# xnemo.net
KiCad netlist of a schematic drawn in EAGLE
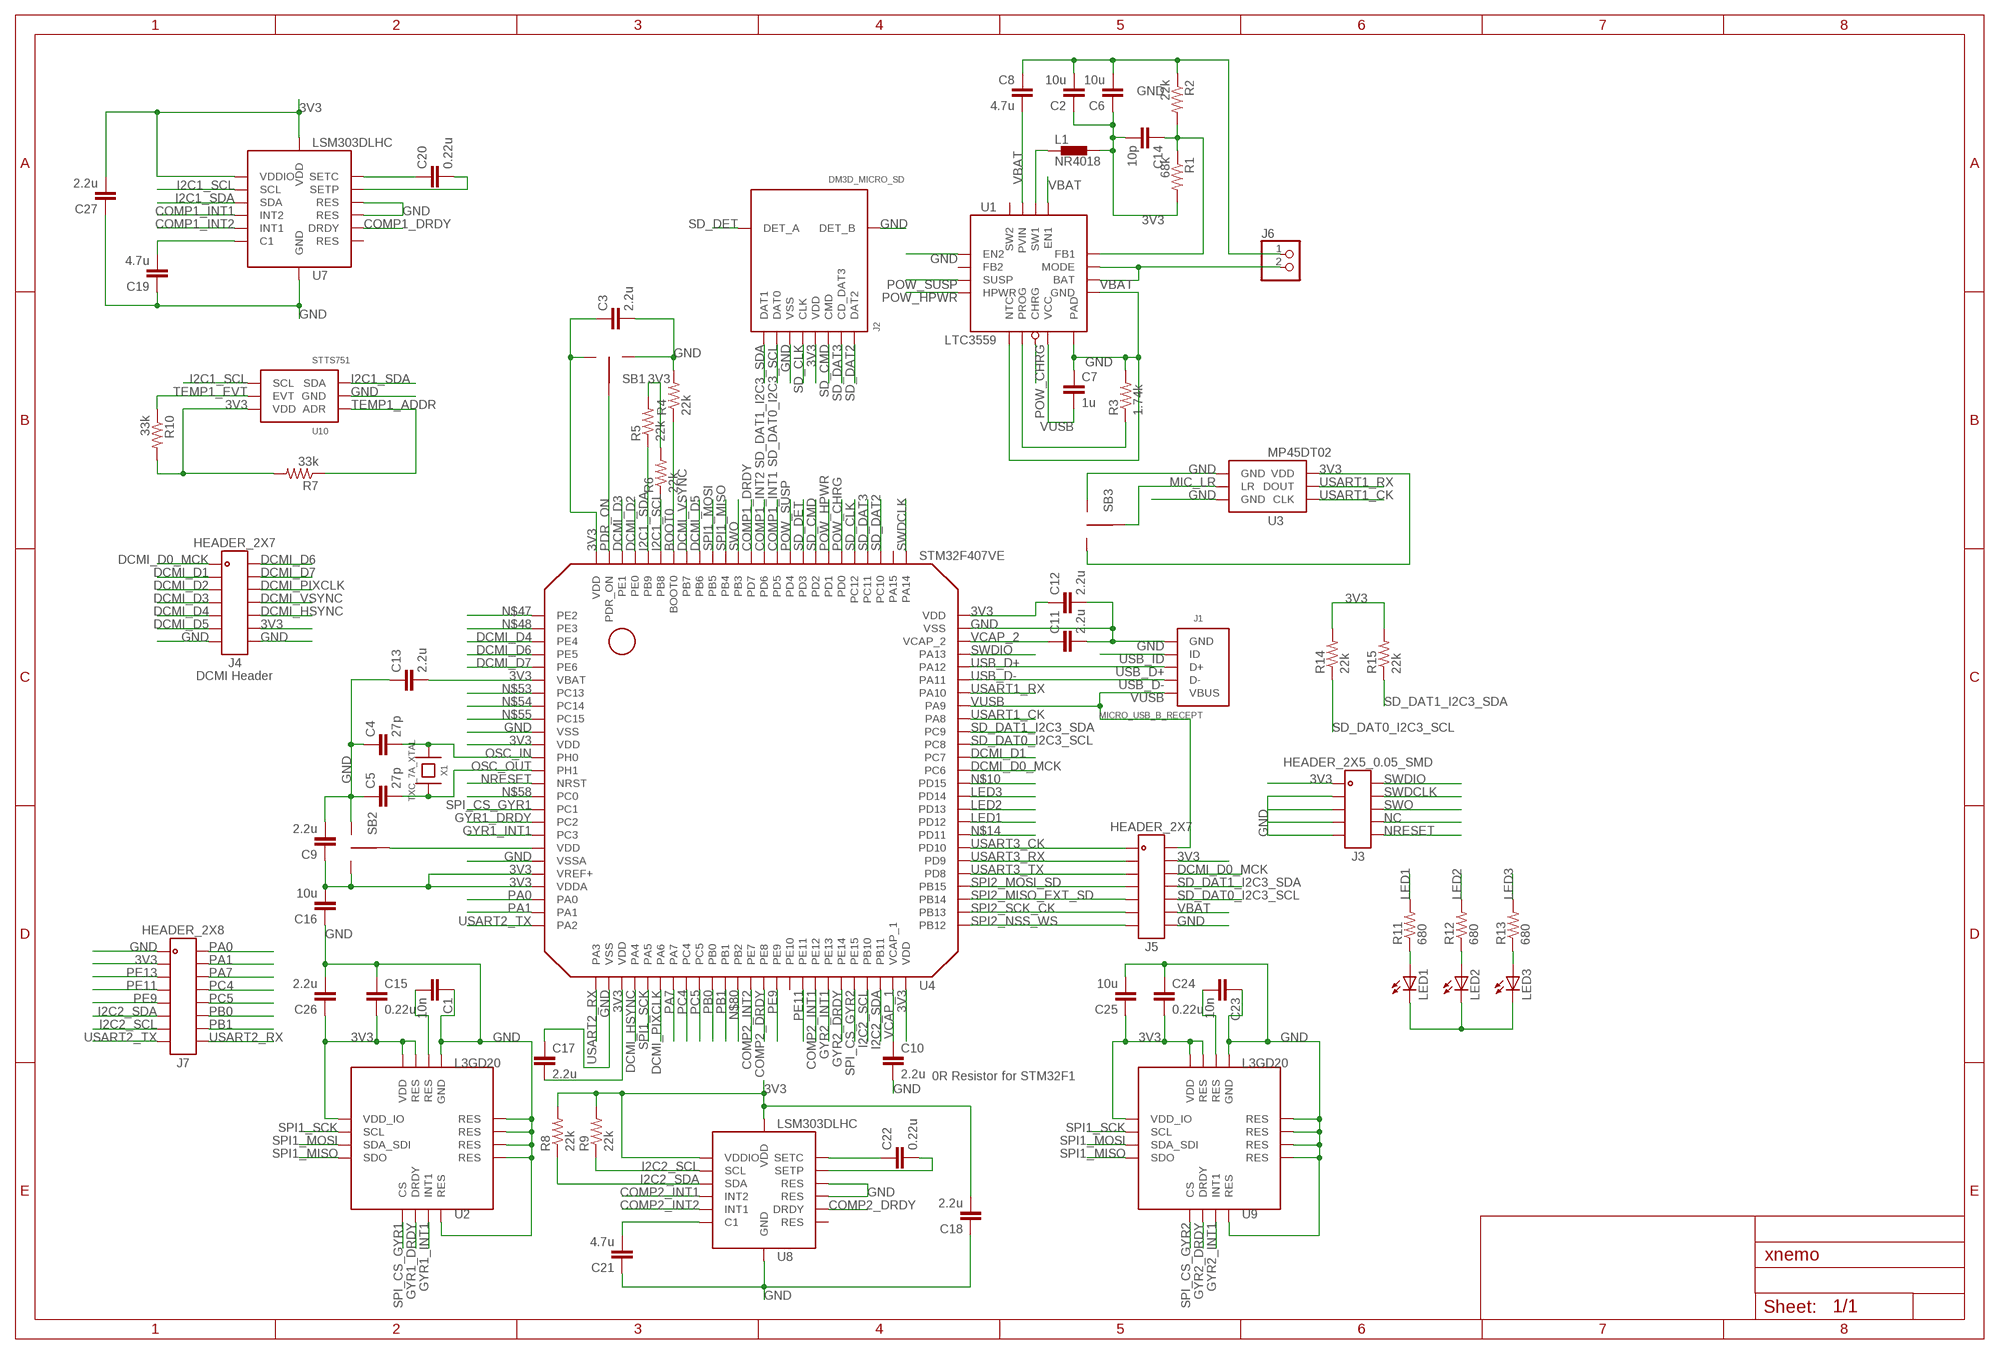
[diagram p0: schematic, sheet 1]

(export (version "E")
  (design (tool "Eeschema 10.0.6"))
  (components
    (comp (ref "C1")
      (value "10n")
      (footprint "eagle-import:C0402")
      (libsource (lib "eagle-import") (part "C-EUC0402"))
    )
    (comp (ref "C2")
      (value "10u")
      (footprint "eagle-import:C0805")
      (libsource (lib "eagle-import") (part "C-EUC0805"))
    )
    (comp (ref "C3")
      (value "2.2u")
      (footprint "eagle-import:C0603")
      (libsource (lib "eagle-import") (part "C-EUC0603"))
    )
    (comp (ref "C4")
      (value "27p")
      (footprint "eagle-import:C0402")
      (libsource (lib "eagle-import") (part "C-EUC0402"))
    )
    (comp (ref "C5")
      (value "27p")
      (footprint "eagle-import:C0402")
      (libsource (lib "eagle-import") (part "C-EUC0402"))
    )
    (comp (ref "C6")
      (value "10u")
      (footprint "eagle-import:C0805")
      (libsource (lib "eagle-import") (part "C-EUC0805"))
    )
    (comp (ref "C7")
      (value "1u")
      (footprint "eagle-import:C0603")
      (libsource (lib "eagle-import") (part "C-EUC0603"))
    )
    (comp (ref "C8")
      (value "4.7u")
      (footprint "eagle-import:C0805")
      (libsource (lib "eagle-import") (part "C-EUC0805"))
    )
    (comp (ref "C9")
      (value "2.2u")
      (footprint "eagle-import:C0603")
      (libsource (lib "eagle-import") (part "C-EUC0603"))
    )
    (comp (ref "C10")
      (value "2.2u")
      (footprint "eagle-import:C0603")
      (libsource (lib "eagle-import") (part "C-EUC0603"))
    )
    (comp (ref "C11")
      (value "2.2u")
      (footprint "eagle-import:C0603")
      (libsource (lib "eagle-import") (part "C-EUC0603"))
    )
    (comp (ref "C12")
      (value "2.2u")
      (footprint "eagle-import:C0603")
      (libsource (lib "eagle-import") (part "C-EUC0603"))
    )
    (comp (ref "C13")
      (value "2.2u")
      (footprint "eagle-import:C0603")
      (libsource (lib "eagle-import") (part "C-EUC0603"))
    )
    (comp (ref "C14")
      (value "10p")
      (footprint "eagle-import:C0402")
      (libsource (lib "eagle-import") (part "C-EUC0402"))
    )
    (comp (ref "C15")
      (value "0.22u")
      (footprint "eagle-import:C0402")
      (libsource (lib "eagle-import") (part "C-EUC0402"))
    )
    (comp (ref "C16")
      (value "10u")
      (footprint "eagle-import:C0805")
      (libsource (lib "eagle-import") (part "C-EUC0805"))
    )
    (comp (ref "C17")
      (value "2.2u")
      (footprint "eagle-import:C0603")
      (libsource (lib "eagle-import") (part "C-EUC0603"))
    )
    (comp (ref "C18")
      (value "2.2u")
      (footprint "eagle-import:C0603")
      (libsource (lib "eagle-import") (part "C-EUC0603"))
    )
    (comp (ref "C19")
      (value "4.7u")
      (footprint "eagle-import:C0805")
      (libsource (lib "eagle-import") (part "C-EUC0805"))
    )
    (comp (ref "C20")
      (value "0.22u")
      (footprint "eagle-import:C0402")
      (libsource (lib "eagle-import") (part "C-EUC0402"))
    )
    (comp (ref "C21")
      (value "4.7u")
      (footprint "eagle-import:C0805")
      (libsource (lib "eagle-import") (part "C-EUC0805"))
    )
    (comp (ref "C22")
      (value "0.22u")
      (footprint "eagle-import:C0402")
      (libsource (lib "eagle-import") (part "C-EUC0402"))
    )
    (comp (ref "C23")
      (value "10n")
      (footprint "eagle-import:C0402")
      (libsource (lib "eagle-import") (part "C-EUC0402"))
    )
    (comp (ref "C24")
      (value "0.22u")
      (footprint "eagle-import:C0402")
      (libsource (lib "eagle-import") (part "C-EUC0402"))
    )
    (comp (ref "C25")
      (value "10u")
      (footprint "eagle-import:C0805")
      (libsource (lib "eagle-import") (part "C-EUC0805"))
    )
    (comp (ref "C26")
      (value "2.2u")
      (footprint "eagle-import:C0603")
      (libsource (lib "eagle-import") (part "C-EUC0603"))
    )
    (comp (ref "C27")
      (value "2.2u")
      (footprint "eagle-import:C0603")
      (libsource (lib "eagle-import") (part "C-EUC0603"))
    )
    (comp (ref "J1")
      (value "MICRO_USB_B_RECEPT")
      (footprint "eagle-import:FCI_MICRO_USB_B")
      (libsource (lib "eagle-import") (part "MICRO_USB_B_RECEPT"))
    )
    (comp (ref "J2")
      (value "DM3D_MICRO_SD")
      (footprint "eagle-import:HIROSE_DM3D")
      (libsource (lib "eagle-import") (part "DM3D_MICRO_SD"))
    )
    (comp (ref "J3")
      (value "HEADER_2X5_0.05_SMD")
      (footprint "eagle-import:HEADER_2X5_0.05_SMD")
      (libsource (lib "eagle-import") (part "HEADER_2X5_0.05_SMD"))
    )
    (comp (ref "J4")
      (value "HEADER_2X7")
      (footprint "eagle-import:HEADER_2X7_0.05X0.1_THRU")
      (libsource (lib "eagle-import") (part "HEADER_2X7"))
    )
    (comp (ref "J5")
      (value "HEADER_2X7")
      (footprint "eagle-import:HEADER_2X7_0.05X0.1_THRU")
      (libsource (lib "eagle-import") (part "HEADER_2X7"))
    )
    (comp (ref "J6")
      (value "PINHD-1X2")
      (footprint "eagle-import:1X02")
      (libsource (lib "eagle-import") (part "PINHD-1X2"))
    )
    (comp (ref "J7")
      (value "HEADER_2X8")
      (footprint "eagle-import:HEADER_2X8_0.05X0.1_THRU")
      (libsource (lib "eagle-import") (part "HEADER_2X8"))
    )
    (comp (ref "L1")
      (value "NR4018")
      (footprint "eagle-import:L_401X")
      (libsource (lib "eagle-import") (part "NR4018"))
    )
    (comp (ref "LED1")
      (value "LEDSML0805")
      (footprint "eagle-import:SML0805")
      (libsource (lib "eagle-import") (part "LEDSML0805"))
    )
    (comp (ref "LED2")
      (value "LEDSML0805")
      (footprint "eagle-import:SML0805")
      (libsource (lib "eagle-import") (part "LEDSML0805"))
    )
    (comp (ref "LED3")
      (value "LEDSML0805")
      (footprint "eagle-import:SML0805")
      (libsource (lib "eagle-import") (part "LEDSML0805"))
    )
    (comp (ref "R1")
      (value "68k")
      (footprint "eagle-import:R0402")
      (libsource (lib "eagle-import") (part "R-US_R0402"))
    )
    (comp (ref "R2")
      (value "22k")
      (footprint "eagle-import:R0402")
      (libsource (lib "eagle-import") (part "R-US_R0402"))
    )
    (comp (ref "R3")
      (value "1.74k")
      (footprint "eagle-import:R0402")
      (libsource (lib "eagle-import") (part "R-US_R0402"))
    )
    (comp (ref "R4")
      (value "22k")
      (footprint "eagle-import:R0402")
      (libsource (lib "eagle-import") (part "R-US_R0402"))
    )
    (comp (ref "R5")
      (value "22k")
      (footprint "eagle-import:R0402")
      (libsource (lib "eagle-import") (part "R-US_R0402"))
    )
    (comp (ref "R6")
      (value "22k")
      (footprint "eagle-import:R0402")
      (libsource (lib "eagle-import") (part "R-US_R0402"))
    )
    (comp (ref "R7")
      (value "33k")
      (footprint "eagle-import:R0402")
      (libsource (lib "eagle-import") (part "R-US_R0402"))
    )
    (comp (ref "R8")
      (value "22k")
      (footprint "eagle-import:R0402")
      (libsource (lib "eagle-import") (part "R-US_R0402"))
    )
    (comp (ref "R9")
      (value "22k")
      (footprint "eagle-import:R0402")
      (libsource (lib "eagle-import") (part "R-US_R0402"))
    )
    (comp (ref "R10")
      (value "33k")
      (footprint "eagle-import:R0402")
      (libsource (lib "eagle-import") (part "R-US_R0402"))
    )
    (comp (ref "R11")
      (value "680")
      (footprint "eagle-import:R0402")
      (libsource (lib "eagle-import") (part "R-US_R0402"))
    )
    (comp (ref "R12")
      (value "680")
      (footprint "eagle-import:R0402")
      (libsource (lib "eagle-import") (part "R-US_R0402"))
    )
    (comp (ref "R13")
      (value "680")
      (footprint "eagle-import:R0402")
      (libsource (lib "eagle-import") (part "R-US_R0402"))
    )
    (comp (ref "R14")
      (value "22k")
      (footprint "eagle-import:R0402")
      (libsource (lib "eagle-import") (part "R-US_R0402"))
    )
    (comp (ref "R15")
      (value "22k")
      (footprint "eagle-import:R0402")
      (libsource (lib "eagle-import") (part "R-US_R0402"))
    )
    (comp (ref "SB1")
      (value "SOLDER_BRIDGE_2")
      (footprint "eagle-import:SOLDER_BRIDGE_2")
      (libsource (lib "eagle-import") (part "SOLDER_BRIDGE_2"))
    )
    (comp (ref "SB2")
      (value "SOLDER_BRIDGE_2")
      (footprint "eagle-import:SOLDER_BRIDGE_2")
      (libsource (lib "eagle-import") (part "SOLDER_BRIDGE_2"))
    )
    (comp (ref "SB3")
      (value "SOLDER_BRIDGE_2")
      (footprint "eagle-import:SOLDER_BRIDGE_2")
      (libsource (lib "eagle-import") (part "SOLDER_BRIDGE_2"))
    )
    (comp (ref "U1")
      (value "LTC3559")
      (footprint "eagle-import:LT_QFN16_3X3")
      (libsource (lib "eagle-import") (part "LTC3559"))
    )
    (comp (ref "U2")
      (value "L3GD20")
      (footprint "eagle-import:ST_LGA16_4X4")
      (libsource (lib "eagle-import") (part "L3GD20"))
    )
    (comp (ref "U3")
      (value "MP45DT02")
      (footprint "eagle-import:ST_HLGA6")
      (libsource (lib "eagle-import") (part "MP45DT02"))
    )
    (comp (ref "U4")
      (value "STM32F407VE")
      (footprint "eagle-import:ST_LQFP100")
      (libsource (lib "eagle-import") (part "STM32F407VE"))
    )
    (comp (ref "U7")
      (value "LSM303DLHC")
      (footprint "eagle-import:ST_LGA14_3X5")
      (libsource (lib "eagle-import") (part "LSM303DLHC"))
    )
    (comp (ref "U8")
      (value "LSM303DLHC")
      (footprint "eagle-import:ST_LGA14_3X5")
      (libsource (lib "eagle-import") (part "LSM303DLHC"))
    )
    (comp (ref "U9")
      (value "L3GD20")
      (footprint "eagle-import:ST_LGA16_4X4")
      (libsource (lib "eagle-import") (part "L3GD20"))
    )
    (comp (ref "U10")
      (value "STTS751")
      (footprint "eagle-import:ST_UDFN-6L_2X2")
      (libsource (lib "eagle-import") (part "STTS751"))
    )
    (comp (ref "X1")
      (value "TXC_7A_XTAL")
      (footprint "eagle-import:TXC_7A_XTAL")
      (libsource (lib "eagle-import") (part "TXC_7A_XTAL"))
    )
  )
  (nets
    (net (code "1") (name "/3V3") (class "Default")
      (node (ref "C12") (pin "1") (pinfunction "1_1") (pintype "passive"))
      (node (ref "C13") (pin "2") (pinfunction "2_2") (pintype "passive"))
      (node (ref "C14") (pin "2") (pinfunction "2_2") (pintype "passive"))
      (node (ref "C15") (pin "2") (pinfunction "2_2") (pintype "passive"))
      (node (ref "C16") (pin "2") (pinfunction "2_2") (pintype "passive"))
      (node (ref "C17") (pin "2") (pinfunction "2_2") (pintype "passive"))
      (node (ref "C18") (pin "2") (pinfunction "2_2") (pintype "passive"))
      (node (ref "C2") (pin "1") (pinfunction "1_1") (pintype "passive"))
      (node (ref "C24") (pin "2") (pinfunction "2_2") (pintype "passive"))
      (node (ref "C25") (pin "1") (pinfunction "1_1") (pintype "passive"))
      (node (ref "C26") (pin "1") (pinfunction "1_1") (pintype "passive"))
      (node (ref "C27") (pin "2") (pinfunction "2_2") (pintype "passive"))
      (node (ref "C3") (pin "1") (pinfunction "1_1") (pintype "passive"))
      (node (ref "C6") (pin "1") (pinfunction "1_1") (pintype "passive"))
      (node (ref "C9") (pin "1") (pinfunction "1_1") (pintype "passive"))
      (node (ref "J2") (pin "P$5") (pinfunction "VDD_P$5") (pintype "bidirectional"))
      (node (ref "J3") (pin "1") (pinfunction "1_1") (pintype "bidirectional"))
      (node (ref "J4") (pin "12") (pinfunction "12_12") (pintype "bidirectional"))
      (node (ref "J5") (pin "4") (pinfunction "4_4") (pintype "bidirectional"))
      (node (ref "J7") (pin "3") (pinfunction "3_3") (pintype "bidirectional"))
      (node (ref "L1") (pin "P$2") (pinfunction "2_P$2") (pintype "passive"))
      (node (ref "R1") (pin "2") (pinfunction "2_2") (pintype "passive"))
      (node (ref "R10") (pin "2") (pinfunction "2_2") (pintype "passive"))
      (node (ref "R14") (pin "2") (pinfunction "2_2") (pintype "passive"))
      (node (ref "R15") (pin "2") (pinfunction "2_2") (pintype "passive"))
      (node (ref "R5") (pin "2") (pinfunction "2_2") (pintype "passive"))
      (node (ref "R6") (pin "2") (pinfunction "2_2") (pintype "passive"))
      (node (ref "R7") (pin "2") (pinfunction "2_2") (pintype "passive"))
      (node (ref "R8") (pin "2") (pinfunction "2_2") (pintype "passive"))
      (node (ref "R9") (pin "2") (pinfunction "2_2") (pintype "passive"))
      (node (ref "SB1") (pin "P$1") (pinfunction "P$1_P$1") (pintype "bidirectional"))
      (node (ref "SB2") (pin "P$1") (pinfunction "P$1_P$1") (pintype "bidirectional"))
      (node (ref "SB3") (pin "P$1") (pinfunction "P$1_P$1") (pintype "bidirectional"))
      (node (ref "U10") (pin "3") (pinfunction "VDD_3") (pintype "bidirectional"))
      (node (ref "U2") (pin "P$1") (pinfunction "VDD_IO_P$1") (pintype "bidirectional"))
      (node (ref "U2") (pin "P$15") (pinfunction "RES_P$15") (pintype "bidirectional"))
      (node (ref "U2") (pin "P$16") (pinfunction "VDD_P$16") (pintype "bidirectional"))
      (node (ref "U3") (pin "6") (pinfunction "VDD_6") (pintype "bidirectional"))
      (node (ref "U4") (pin "P$100") (pinfunction "VDD_P$100") (pintype "bidirectional"))
      (node (ref "U4") (pin "P$11") (pinfunction "VDD_P$11") (pintype "bidirectional"))
      (node (ref "U4") (pin "P$21") (pinfunction "VREF+_P$21") (pintype "bidirectional"))
      (node (ref "U4") (pin "P$22") (pinfunction "VDDA_P$22") (pintype "bidirectional"))
      (node (ref "U4") (pin "P$28") (pinfunction "VDD_P$28") (pintype "bidirectional"))
      (node (ref "U4") (pin "P$50") (pinfunction "VDD_P$50") (pintype "bidirectional"))
      (node (ref "U4") (pin "P$6") (pinfunction "VBAT_P$6") (pintype "bidirectional"))
      (node (ref "U4") (pin "P$75") (pinfunction "VDD_P$75") (pintype "bidirectional"))
      (node (ref "U7") (pin "P$1") (pinfunction "VDDIO_P$1") (pintype "input"))
      (node (ref "U7") (pin "P$14") (pinfunction "VDD_P$14") (pintype "power_in"))
      (node (ref "U8") (pin "P$1") (pinfunction "VDDIO_P$1") (pintype "input"))
      (node (ref "U8") (pin "P$14") (pinfunction "VDD_P$14") (pintype "power_in"))
      (node (ref "U9") (pin "P$1") (pinfunction "VDD_IO_P$1") (pintype "bidirectional"))
      (node (ref "U9") (pin "P$15") (pinfunction "RES_P$15") (pintype "bidirectional"))
      (node (ref "U9") (pin "P$16") (pinfunction "VDD_P$16") (pintype "bidirectional"))
    )
    (net (code "2") (name "/BOOT0") (class "Default")
      (node (ref "R4") (pin "1") (pinfunction "1_1") (pintype "passive"))
      (node (ref "U4") (pin "P$94") (pinfunction "BOOT0_P$94") (pintype "bidirectional"))
    )
    (net (code "3") (name "/COMP1_DRDY") (class "Default")
      (node (ref "U4") (pin "P$88") (pinfunction "PD7_P$88") (pintype "bidirectional"))
      (node (ref "U7") (pin "P$9") (pinfunction "DRDY_P$9") (pintype "output"))
    )
    (net (code "4") (name "/COMP1_INT1") (class "Default")
      (node (ref "U4") (pin "P$86") (pinfunction "PD5_P$86") (pintype "bidirectional"))
      (node (ref "U7") (pin "P$4") (pinfunction "INT2_P$4") (pintype "output"))
    )
    (net (code "5") (name "/COMP1_INT2") (class "Default")
      (node (ref "U4") (pin "P$87") (pinfunction "PD6_P$87") (pintype "bidirectional"))
      (node (ref "U7") (pin "P$5") (pinfunction "INT1_P$5") (pintype "output"))
    )
    (net (code "6") (name "/COMP2_DRDY") (class "Default")
      (node (ref "U4") (pin "P$39") (pinfunction "PE8_P$39") (pintype "bidirectional"))
      (node (ref "U8") (pin "P$9") (pinfunction "DRDY_P$9") (pintype "output"))
    )
    (net (code "7") (name "/COMP2_INT1") (class "Default")
      (node (ref "U4") (pin "P$43") (pinfunction "PE12_P$43") (pintype "bidirectional"))
      (node (ref "U8") (pin "P$4") (pinfunction "INT2_P$4") (pintype "output"))
    )
    (net (code "8") (name "/COMP2_INT2") (class "Default")
      (node (ref "U4") (pin "P$38") (pinfunction "PE7_P$38") (pintype "bidirectional"))
      (node (ref "U8") (pin "P$5") (pinfunction "INT1_P$5") (pintype "output"))
    )
    (net (code "9") (name "/DCMI_D0_MCK") (class "Default")
      (node (ref "J4") (pin "1") (pinfunction "1_1") (pintype "bidirectional"))
      (node (ref "J5") (pin "6") (pinfunction "6_6") (pintype "bidirectional"))
      (node (ref "U4") (pin "P$63") (pinfunction "PC6_P$63") (pintype "bidirectional"))
    )
    (net (code "10") (name "/DCMI_D1") (class "Default")
      (node (ref "J4") (pin "3") (pinfunction "3_3") (pintype "bidirectional"))
      (node (ref "U4") (pin "P$64") (pinfunction "PC7_P$64") (pintype "bidirectional"))
    )
    (net (code "11") (name "/DCMI_D2") (class "Default")
      (node (ref "J4") (pin "5") (pinfunction "5_5") (pintype "bidirectional"))
      (node (ref "U4") (pin "P$97") (pinfunction "PE0_P$97") (pintype "bidirectional"))
    )
    (net (code "12") (name "/DCMI_D3") (class "Default")
      (node (ref "J4") (pin "7") (pinfunction "7_7") (pintype "bidirectional"))
      (node (ref "U4") (pin "P$98") (pinfunction "PE1_P$98") (pintype "bidirectional"))
    )
    (net (code "13") (name "/DCMI_D4") (class "Default")
      (node (ref "J4") (pin "9") (pinfunction "9_9") (pintype "bidirectional"))
      (node (ref "U4") (pin "P$3") (pinfunction "PE4_P$3") (pintype "bidirectional"))
    )
    (net (code "14") (name "/DCMI_D5") (class "Default")
      (node (ref "J4") (pin "11") (pinfunction "11_11") (pintype "bidirectional"))
      (node (ref "U4") (pin "P$92") (pinfunction "PB6_P$92") (pintype "bidirectional"))
    )
    (net (code "15") (name "/DCMI_D6") (class "Default")
      (node (ref "J4") (pin "2") (pinfunction "2_2") (pintype "bidirectional"))
      (node (ref "U4") (pin "P$4") (pinfunction "PE5_P$4") (pintype "bidirectional"))
    )
    (net (code "16") (name "/DCMI_D7") (class "Default")
      (node (ref "J4") (pin "4") (pinfunction "4_4") (pintype "bidirectional"))
      (node (ref "U4") (pin "P$5") (pinfunction "PE6_P$5") (pintype "bidirectional"))
    )
    (net (code "17") (name "/DCMI_HSYNC") (class "Default")
      (node (ref "J4") (pin "10") (pinfunction "10_10") (pintype "bidirectional"))
      (node (ref "U4") (pin "P$29") (pinfunction "PA4_P$29") (pintype "bidirectional"))
    )
    (net (code "18") (name "/DCMI_PIXCLK") (class "Default")
      (node (ref "J4") (pin "6") (pinfunction "6_6") (pintype "bidirectional"))
      (node (ref "U4") (pin "P$31") (pinfunction "PA6_P$31") (pintype "bidirectional"))
    )
    (net (code "19") (name "/DCMI_VSYNC") (class "Default")
      (node (ref "J4") (pin "8") (pinfunction "8_8") (pintype "bidirectional"))
      (node (ref "U4") (pin "P$93") (pinfunction "PB7_P$93") (pintype "bidirectional"))
    )
    (net (code "20") (name "/GND") (class "Default")
      (node (ref "C1") (pin "1") (pinfunction "1_1") (pintype "passive"))
      (node (ref "C10") (pin "2") (pinfunction "2_2") (pintype "passive"))
      (node (ref "C11") (pin "2") (pinfunction "2_2") (pintype "passive"))
      (node (ref "C12") (pin "2") (pinfunction "2_2") (pintype "passive"))
      (node (ref "C13") (pin "1") (pinfunction "1_1") (pintype "passive"))
      (node (ref "C15") (pin "1") (pinfunction "1_1") (pintype "passive"))
      (node (ref "C16") (pin "1") (pinfunction "1_1") (pintype "passive"))
      (node (ref "C17") (pin "1") (pinfunction "1_1") (pintype "passive"))
      (node (ref "C18") (pin "1") (pinfunction "1_1") (pintype "passive"))
      (node (ref "C19") (pin "1") (pinfunction "1_1") (pintype "passive"))
      (node (ref "C2") (pin "2") (pinfunction "2_2") (pintype "passive"))
      (node (ref "C21") (pin "1") (pinfunction "1_1") (pintype "passive"))
      (node (ref "C23") (pin "1") (pinfunction "1_1") (pintype "passive"))
      (node (ref "C24") (pin "1") (pinfunction "1_1") (pintype "passive"))
      (node (ref "C25") (pin "2") (pinfunction "2_2") (pintype "passive"))
      (node (ref "C26") (pin "2") (pinfunction "2_2") (pintype "passive"))
      (node (ref "C27") (pin "1") (pinfunction "1_1") (pintype "passive"))
      (node (ref "C3") (pin "2") (pinfunction "2_2") (pintype "passive"))
      (node (ref "C4") (pin "1") (pinfunction "1_1") (pintype "passive"))
      (node (ref "C5") (pin "1") (pinfunction "1_1") (pintype "passive"))
      (node (ref "C6") (pin "2") (pinfunction "2_2") (pintype "passive"))
      (node (ref "C7") (pin "1") (pinfunction "1_1") (pintype "passive"))
      (node (ref "C8") (pin "1") (pinfunction "1_1") (pintype "passive"))
      (node (ref "C9") (pin "2") (pinfunction "2_2") (pintype "passive"))
      (node (ref "J1") (pin "P$5") (pinfunction "GND_P$5") (pintype "bidirectional"))
      (node (ref "J2") (pin "P$3") (pinfunction "VSS_P$3") (pintype "bidirectional"))
      (node (ref "J2") (pin "P$9") (pinfunction "DET_B_P$9") (pintype "bidirectional"))
      (node (ref "J3") (pin "3") (pinfunction "3_3") (pintype "bidirectional"))
      (node (ref "J3") (pin "5") (pinfunction "5_5") (pintype "bidirectional"))
      (node (ref "J3") (pin "7") (pinfunction "7_7") (pintype "bidirectional"))
      (node (ref "J3") (pin "9") (pinfunction "9_9") (pintype "bidirectional"))
      (node (ref "J4") (pin "13") (pinfunction "13_13") (pintype "bidirectional"))
      (node (ref "J4") (pin "14") (pinfunction "14_14") (pintype "bidirectional"))
      (node (ref "J5") (pin "14") (pinfunction "14_14") (pintype "bidirectional"))
      (node (ref "J6") (pin "1") (pinfunction "1_1") (pintype "passive"))
      (node (ref "J7") (pin "1") (pinfunction "1_1") (pintype "bidirectional"))
      (node (ref "LED1") (pin "C") (pinfunction "C_C") (pintype "passive"))
      (node (ref "LED2") (pin "C") (pinfunction "C_C") (pintype "passive"))
      (node (ref "LED3") (pin "C") (pinfunction "C_C") (pintype "passive"))
      (node (ref "R2") (pin "1") (pinfunction "1_1") (pintype "passive"))
      (node (ref "R3") (pin "2") (pinfunction "2_2") (pintype "passive"))
      (node (ref "R4") (pin "2") (pinfunction "2_2") (pintype "passive"))
      (node (ref "SB1") (pin "P$3") (pinfunction "P$2_P$3") (pintype "bidirectional"))
      (node (ref "SB2") (pin "P$3") (pinfunction "P$2_P$3") (pintype "bidirectional"))
      (node (ref "SB3") (pin "P$3") (pinfunction "P$2_P$3") (pintype "bidirectional"))
      (node (ref "U1") (pin "P$1") (pinfunction "GND_P$1") (pintype "bidirectional"))
      (node (ref "U1") (pin "P$13") (pinfunction "NTC_P$13") (pintype "bidirectional"))
      (node (ref "U1") (pin "P$17") (pinfunction "PAD_P$17") (pintype "bidirectional"))
      (node (ref "U1") (pin "P$9") (pinfunction "EN2_P$9") (pintype "bidirectional"))
      (node (ref "U10") (pin "5") (pinfunction "GND_5") (pintype "bidirectional"))
      (node (ref "U2") (pin "P$10") (pinfunction "RES_P$10") (pintype "bidirectional"))
      (node (ref "U2") (pin "P$11") (pinfunction "RES_P$11") (pintype "bidirectional"))
      (node (ref "U2") (pin "P$12") (pinfunction "RES_P$12") (pintype "bidirectional"))
      (node (ref "U2") (pin "P$13") (pinfunction "GND_P$13") (pintype "bidirectional"))
      (node (ref "U2") (pin "P$8") (pinfunction "RES_P$8") (pintype "bidirectional"))
      (node (ref "U2") (pin "P$9") (pinfunction "RES_P$9") (pintype "bidirectional"))
      (node (ref "U3") (pin "1") (pinfunction "GND_1") (pintype "bidirectional"))
      (node (ref "U3") (pin "3") (pinfunction "GND_3") (pintype "bidirectional"))
      (node (ref "U4") (pin "P$10") (pinfunction "VSS_P$10") (pintype "bidirectional"))
      (node (ref "U4") (pin "P$20") (pinfunction "VSSA_P$20") (pintype "bidirectional"))
      (node (ref "U4") (pin "P$27") (pinfunction "VSS_P$27") (pintype "bidirectional"))
      (node (ref "U4") (pin "P$74") (pinfunction "VSS_P$74") (pintype "bidirectional"))
      (node (ref "U7") (pin "P$10") (pinfunction "RES_P$10") (pintype "bidirectional"))
      (node (ref "U7") (pin "P$11") (pinfunction "RES_P$11") (pintype "bidirectional"))
      (node (ref "U7") (pin "P$7") (pinfunction "GND_P$7") (pintype "power_in"))
      (node (ref "U8") (pin "P$10") (pinfunction "RES_P$10") (pintype "bidirectional"))
      (node (ref "U8") (pin "P$11") (pinfunction "RES_P$11") (pintype "bidirectional"))
      (node (ref "U8") (pin "P$7") (pinfunction "GND_P$7") (pintype "power_in"))
      (node (ref "U9") (pin "P$10") (pinfunction "RES_P$10") (pintype "bidirectional"))
      (node (ref "U9") (pin "P$11") (pinfunction "RES_P$11") (pintype "bidirectional"))
      (node (ref "U9") (pin "P$12") (pinfunction "RES_P$12") (pintype "bidirectional"))
      (node (ref "U9") (pin "P$13") (pinfunction "GND_P$13") (pintype "bidirectional"))
      (node (ref "U9") (pin "P$8") (pinfunction "RES_P$8") (pintype "bidirectional"))
      (node (ref "U9") (pin "P$9") (pinfunction "RES_P$9") (pintype "bidirectional"))
    )
    (net (code "21") (name "/GYR1_DRDY") (class "Default")
      (node (ref "U2") (pin "P$6") (pinfunction "DRDY_P$6") (pintype "bidirectional"))
      (node (ref "U4") (pin "P$17") (pinfunction "PC2_P$17") (pintype "bidirectional"))
    )
    (net (code "22") (name "/GYR1_INT1") (class "Default")
      (node (ref "U2") (pin "P$7") (pinfunction "INT1_P$7") (pintype "bidirectional"))
      (node (ref "U4") (pin "P$18") (pinfunction "PC3_P$18") (pintype "bidirectional"))
    )
    (net (code "23") (name "/GYR2_DRDY") (class "Default")
      (node (ref "U4") (pin "P$45") (pinfunction "PE14_P$45") (pintype "bidirectional"))
      (node (ref "U9") (pin "P$6") (pinfunction "DRDY_P$6") (pintype "bidirectional"))
    )
    (net (code "24") (name "/GYR2_INT1") (class "Default")
      (node (ref "U4") (pin "P$44") (pinfunction "PE13_P$44") (pintype "bidirectional"))
      (node (ref "U9") (pin "P$7") (pinfunction "INT1_P$7") (pintype "bidirectional"))
    )
    (net (code "25") (name "/I2C1_SCL") (class "Default")
      (node (ref "R6") (pin "1") (pinfunction "1_1") (pintype "passive"))
      (node (ref "U10") (pin "1") (pinfunction "SCL_1") (pintype "bidirectional"))
      (node (ref "U4") (pin "P$95") (pinfunction "PB8_P$95") (pintype "bidirectional"))
      (node (ref "U7") (pin "P$2") (pinfunction "SCL_P$2") (pintype "bidirectional"))
    )
    (net (code "26") (name "/I2C1_SDA") (class "Default")
      (node (ref "R5") (pin "1") (pinfunction "1_1") (pintype "passive"))
      (node (ref "U10") (pin "6") (pinfunction "SDA_6") (pintype "bidirectional"))
      (node (ref "U4") (pin "P$96") (pinfunction "PB9_P$96") (pintype "bidirectional"))
      (node (ref "U7") (pin "P$3") (pinfunction "SDA_P$3") (pintype "bidirectional"))
    )
    (net (code "27") (name "/I2C2_SCL") (class "Default")
      (node (ref "J7") (pin "13") (pinfunction "13_13") (pintype "bidirectional"))
      (node (ref "R9") (pin "1") (pinfunction "1_1") (pintype "passive"))
      (node (ref "U4") (pin "P$47") (pinfunction "PB10_P$47") (pintype "bidirectional"))
      (node (ref "U8") (pin "P$2") (pinfunction "SCL_P$2") (pintype "bidirectional"))
    )
    (net (code "28") (name "/I2C2_SDA") (class "Default")
      (node (ref "J7") (pin "11") (pinfunction "11_11") (pintype "bidirectional"))
      (node (ref "R8") (pin "1") (pinfunction "1_1") (pintype "passive"))
      (node (ref "U4") (pin "P$48") (pinfunction "PB11_P$48") (pintype "bidirectional"))
      (node (ref "U8") (pin "P$3") (pinfunction "SDA_P$3") (pintype "bidirectional"))
    )
    (net (code "29") (name "/LED1") (class "Default")
      (node (ref "R11") (pin "2") (pinfunction "2_2") (pintype "passive"))
      (node (ref "U4") (pin "P$59") (pinfunction "PD12_P$59") (pintype "bidirectional"))
    )
    (net (code "30") (name "/LED2") (class "Default")
      (node (ref "R12") (pin "2") (pinfunction "2_2") (pintype "passive"))
      (node (ref "U4") (pin "P$60") (pinfunction "PD13_P$60") (pintype "bidirectional"))
    )
    (net (code "31") (name "/LED3") (class "Default")
      (node (ref "R13") (pin "2") (pinfunction "2_2") (pintype "passive"))
      (node (ref "U4") (pin "P$61") (pinfunction "PD14_P$61") (pintype "bidirectional"))
    )
    (net (code "32") (name "/MIC_LR") (class "Default")
      (node (ref "SB3") (pin "P$2") (pinfunction "P$3_P$2") (pintype "bidirectional"))
      (node (ref "U3") (pin "2") (pinfunction "LR_2") (pintype "bidirectional"))
    )
    (net (code "33") (name "/N$10") (class "Default")
      (node (ref "U4") (pin "P$62") (pinfunction "PD15_P$62") (pintype "bidirectional"))
    )
    (net (code "34") (name "/N$14") (class "Default")
      (node (ref "U4") (pin "P$58") (pinfunction "PD11_P$58") (pintype "bidirectional"))
    )
    (net (code "35") (name "/N$47") (class "Default")
      (node (ref "U4") (pin "P$1") (pinfunction "PE2_P$1") (pintype "bidirectional"))
    )
    (net (code "36") (name "/N$48") (class "Default")
      (node (ref "U4") (pin "P$2") (pinfunction "PE3_P$2") (pintype "bidirectional"))
    )
    (net (code "37") (name "/N$53") (class "Default")
      (node (ref "U4") (pin "P$7") (pinfunction "PC13_P$7") (pintype "bidirectional"))
    )
    (net (code "38") (name "/N$54") (class "Default")
      (node (ref "U4") (pin "P$8") (pinfunction "PC14_P$8") (pintype "bidirectional"))
    )
    (net (code "39") (name "/N$55") (class "Default")
      (node (ref "U4") (pin "P$9") (pinfunction "PC15_P$9") (pintype "bidirectional"))
    )
    (net (code "40") (name "/N$58") (class "Default")
      (node (ref "U4") (pin "P$15") (pinfunction "PC0_P$15") (pintype "bidirectional"))
    )
    (net (code "41") (name "/N$80") (class "Default")
      (node (ref "U4") (pin "P$37") (pinfunction "PB2_P$37") (pintype "bidirectional"))
    )
    (net (code "42") (name "/NC") (class "Default")
      (node (ref "J3") (pin "8") (pinfunction "8_8") (pintype "bidirectional"))
    )
    (net (code "43") (name "/NRESET") (class "Default")
      (node (ref "J3") (pin "10") (pinfunction "10_10") (pintype "bidirectional"))
      (node (ref "U4") (pin "P$14") (pinfunction "NRST_P$14") (pintype "bidirectional"))
    )
    (net (code "44") (name "/OSC_IN") (class "Default")
      (node (ref "C4") (pin "2") (pinfunction "2_2") (pintype "passive"))
      (node (ref "U4") (pin "P$12") (pinfunction "PH0_P$12") (pintype "bidirectional"))
      (node (ref "X1") (pin "P$2") (pinfunction "P$2_P$2") (pintype "bidirectional"))
    )
    (net (code "45") (name "/OSC_OUT") (class "Default")
      (node (ref "C5") (pin "2") (pinfunction "2_2") (pintype "passive"))
      (node (ref "U4") (pin "P$13") (pinfunction "PH1_P$13") (pintype "bidirectional"))
      (node (ref "X1") (pin "P$1") (pinfunction "P$1_P$1") (pintype "bidirectional"))
    )
    (net (code "46") (name "/PA0") (class "Default")
      (node (ref "J7") (pin "2") (pinfunction "2_2") (pintype "bidirectional"))
      (node (ref "U4") (pin "P$23") (pinfunction "PA0_P$23") (pintype "bidirectional"))
    )
    (net (code "47") (name "/PA1") (class "Default")
      (node (ref "J7") (pin "4") (pinfunction "4_4") (pintype "bidirectional"))
      (node (ref "U4") (pin "P$24") (pinfunction "PA1_P$24") (pintype "bidirectional"))
    )
    (net (code "48") (name "/PA7") (class "Default")
      (node (ref "J7") (pin "6") (pinfunction "6_6") (pintype "bidirectional"))
      (node (ref "U4") (pin "P$32") (pinfunction "PA7_P$32") (pintype "bidirectional"))
    )
    (net (code "49") (name "/PB0") (class "Default")
      (node (ref "J7") (pin "12") (pinfunction "12_12") (pintype "bidirectional"))
      (node (ref "U4") (pin "P$35") (pinfunction "PB0_P$35") (pintype "bidirectional"))
    )
    (net (code "50") (name "/PB1") (class "Default")
      (node (ref "J7") (pin "14") (pinfunction "14_14") (pintype "bidirectional"))
      (node (ref "U4") (pin "P$36") (pinfunction "PB1_P$36") (pintype "bidirectional"))
    )
    (net (code "51") (name "/PC4") (class "Default")
      (node (ref "J7") (pin "8") (pinfunction "8_8") (pintype "bidirectional"))
      (node (ref "U4") (pin "P$33") (pinfunction "PC4_P$33") (pintype "bidirectional"))
    )
    (net (code "52") (name "/PC5") (class "Default")
      (node (ref "J7") (pin "10") (pinfunction "10_10") (pintype "bidirectional"))
      (node (ref "U4") (pin "P$34") (pinfunction "PC5_P$34") (pintype "bidirectional"))
    )
    (net (code "53") (name "/PDR_ON") (class "Default")
      (node (ref "SB1") (pin "P$2") (pinfunction "P$3_P$2") (pintype "bidirectional"))
      (node (ref "U4") (pin "P$99") (pinfunction "PDR_ON_P$99") (pintype "bidirectional"))
    )
    (net (code "54") (name "/PE9") (class "Default")
      (node (ref "J7") (pin "9") (pinfunction "9_9") (pintype "bidirectional"))
      (node (ref "U4") (pin "P$40") (pinfunction "PE9_P$40") (pintype "bidirectional"))
    )
    (net (code "55") (name "/PE11") (class "Default")
      (node (ref "J7") (pin "7") (pinfunction "7_7") (pintype "bidirectional"))
      (node (ref "U4") (pin "P$42") (pinfunction "PE11_P$42") (pintype "bidirectional"))
    )
    (net (code "56") (name "/PE13") (class "Default")
      (node (ref "J7") (pin "5") (pinfunction "5_5") (pintype "bidirectional"))
    )
    (net (code "57") (name "/POW_CHRG") (class "Default")
      (node (ref "U1") (pin "P$15") (pinfunction "CHRG_P$15") (pintype "bidirectional"))
      (node (ref "U4") (pin "P$81") (pinfunction "PD0_P$81") (pintype "bidirectional"))
    )
    (net (code "58") (name "/POW_HPWR") (class "Default")
      (node (ref "U1") (pin "P$12") (pinfunction "HPWR_P$12") (pintype "bidirectional"))
      (node (ref "U4") (pin "P$82") (pinfunction "PD1_P$82") (pintype "bidirectional"))
    )
    (net (code "59") (name "/POW_SUSP") (class "Default")
      (node (ref "U1") (pin "P$11") (pinfunction "SUSP_P$11") (pintype "bidirectional"))
      (node (ref "U4") (pin "P$85") (pinfunction "PD4_P$85") (pintype "bidirectional"))
    )
    (net (code "60") (name "/SD_CLK") (class "Default")
      (node (ref "J2") (pin "P$4") (pinfunction "CLK_P$4") (pintype "bidirectional"))
      (node (ref "U4") (pin "P$80") (pinfunction "PC12_P$80") (pintype "bidirectional"))
    )
    (net (code "61") (name "/SD_CMD") (class "Default")
      (node (ref "J2") (pin "P$6") (pinfunction "CMD_P$6") (pintype "bidirectional"))
      (node (ref "U4") (pin "P$83") (pinfunction "PD2_P$83") (pintype "bidirectional"))
    )
    (net (code "62") (name "/SD_DAT0_I2C3_SCL") (class "Default")
      (node (ref "J2") (pin "P$2") (pinfunction "DAT0_P$2") (pintype "bidirectional"))
      (node (ref "J5") (pin "10") (pinfunction "10_10") (pintype "bidirectional"))
      (node (ref "R14") (pin "1") (pinfunction "1_1") (pintype "passive"))
      (node (ref "U4") (pin "P$65") (pinfunction "PC8_P$65") (pintype "bidirectional"))
    )
    (net (code "63") (name "/SD_DAT1_I2C3_SDA") (class "Default")
      (node (ref "J2") (pin "P$1") (pinfunction "DAT1_P$1") (pintype "bidirectional"))
      (node (ref "J5") (pin "8") (pinfunction "8_8") (pintype "bidirectional"))
      (node (ref "R15") (pin "1") (pinfunction "1_1") (pintype "passive"))
      (node (ref "U4") (pin "P$66") (pinfunction "PC9_P$66") (pintype "bidirectional"))
    )
    (net (code "64") (name "/SD_DAT2") (class "Default")
      (node (ref "J2") (pin "P$8") (pinfunction "DAT2_P$8") (pintype "bidirectional"))
      (node (ref "U4") (pin "P$78") (pinfunction "PC10_P$78") (pintype "bidirectional"))
    )
    (net (code "65") (name "/SD_DAT3") (class "Default")
      (node (ref "J2") (pin "P$7") (pinfunction "CD_DAT3_P$7") (pintype "bidirectional"))
      (node (ref "U4") (pin "P$79") (pinfunction "PC11_P$79") (pintype "bidirectional"))
    )
    (net (code "66") (name "/SD_DET") (class "Default")
      (node (ref "J2") (pin "P$10") (pinfunction "DET_A_P$10") (pintype "bidirectional"))
      (node (ref "U4") (pin "P$84") (pinfunction "PD3_P$84") (pintype "bidirectional"))
    )
    (net (code "67") (name "/SPI1_MISO") (class "Default")
      (node (ref "U2") (pin "P$4") (pinfunction "SDO_P$4") (pintype "bidirectional"))
      (node (ref "U4") (pin "P$90") (pinfunction "PB4_P$90") (pintype "bidirectional"))
      (node (ref "U9") (pin "P$4") (pinfunction "SDO_P$4") (pintype "bidirectional"))
    )
    (net (code "68") (name "/SPI1_MOSI") (class "Default")
      (node (ref "U2") (pin "P$3") (pinfunction "SDA_SDI_P$3") (pintype "bidirectional"))
      (node (ref "U4") (pin "P$91") (pinfunction "PB5_P$91") (pintype "bidirectional"))
      (node (ref "U9") (pin "P$3") (pinfunction "SDA_SDI_P$3") (pintype "bidirectional"))
    )
    (net (code "69") (name "/SPI1_SCK") (class "Default")
      (node (ref "U2") (pin "P$2") (pinfunction "SCL_P$2") (pintype "bidirectional"))
      (node (ref "U4") (pin "P$30") (pinfunction "PA5_P$30") (pintype "bidirectional"))
      (node (ref "U9") (pin "P$2") (pinfunction "SCL_P$2") (pintype "bidirectional"))
    )
    (net (code "70") (name "/SPI2_MISO_EXT_SD") (class "Default")
      (node (ref "J5") (pin "9") (pinfunction "9_9") (pintype "bidirectional"))
      (node (ref "U4") (pin "P$53") (pinfunction "PB14_P$53") (pintype "bidirectional"))
    )
    (net (code "71") (name "/SPI2_MOSI_SD") (class "Default")
      (node (ref "J5") (pin "7") (pinfunction "7_7") (pintype "bidirectional"))
      (node (ref "U4") (pin "P$54") (pinfunction "PB15_P$54") (pintype "bidirectional"))
    )
    (net (code "72") (name "/SPI2_NSS_WS") (class "Default")
      (node (ref "J5") (pin "13") (pinfunction "13_13") (pintype "bidirectional"))
      (node (ref "U4") (pin "P$51") (pinfunction "PB12_P$51") (pintype "bidirectional"))
    )
    (net (code "73") (name "/SPI2_SCK_CK") (class "Default")
      (node (ref "J5") (pin "11") (pinfunction "11_11") (pintype "bidirectional"))
      (node (ref "U4") (pin "P$52") (pinfunction "PB13_P$52") (pintype "bidirectional"))
    )
    (net (code "74") (name "/SPI_CS_GYR1") (class "Default")
      (node (ref "U2") (pin "P$5") (pinfunction "CS_P$5") (pintype "bidirectional"))
      (node (ref "U4") (pin "P$16") (pinfunction "PC1_P$16") (pintype "bidirectional"))
    )
    (net (code "75") (name "/SPI_CS_GYR2") (class "Default")
      (node (ref "U4") (pin "P$46") (pinfunction "PE15_P$46") (pintype "bidirectional"))
      (node (ref "U9") (pin "P$5") (pinfunction "CS_P$5") (pintype "bidirectional"))
    )
    (net (code "76") (name "/SWDCLK") (class "Default")
      (node (ref "J3") (pin "4") (pinfunction "4_4") (pintype "bidirectional"))
      (node (ref "U4") (pin "P$76") (pinfunction "PA14_P$76") (pintype "bidirectional"))
    )
    (net (code "77") (name "/SWDIO") (class "Default")
      (node (ref "J3") (pin "2") (pinfunction "2_2") (pintype "bidirectional"))
      (node (ref "U4") (pin "P$72") (pinfunction "PA13_P$72") (pintype "bidirectional"))
    )
    (net (code "78") (name "/SWO") (class "Default")
      (node (ref "J3") (pin "6") (pinfunction "6_6") (pintype "bidirectional"))
      (node (ref "U4") (pin "P$89") (pinfunction "PB3_P$89") (pintype "bidirectional"))
    )
    (net (code "79") (name "/TEMP1_ADDR") (class "Default")
      (node (ref "R7") (pin "1") (pinfunction "1_1") (pintype "passive"))
      (node (ref "U10") (pin "4") (pinfunction "ADR_4") (pintype "bidirectional"))
    )
    (net (code "80") (name "/TEMP1_EVT") (class "Default")
      (node (ref "R10") (pin "1") (pinfunction "1_1") (pintype "passive"))
      (node (ref "U10") (pin "2") (pinfunction "EVT_2") (pintype "bidirectional"))
    )
    (net (code "81") (name "/USART1_CK") (class "Default")
      (node (ref "U3") (pin "4") (pinfunction "CLK_4") (pintype "bidirectional"))
      (node (ref "U4") (pin "P$67") (pinfunction "PA8_P$67") (pintype "bidirectional"))
    )
    (net (code "82") (name "/USART1_RX") (class "Default")
      (node (ref "U3") (pin "5") (pinfunction "DOUT_5") (pintype "bidirectional"))
      (node (ref "U4") (pin "P$69") (pinfunction "PA10_P$69") (pintype "bidirectional"))
    )
    (net (code "83") (name "/USART2_RX") (class "Default")
      (node (ref "J7") (pin "16") (pinfunction "16_16") (pintype "bidirectional"))
      (node (ref "U4") (pin "P$26") (pinfunction "PA3_P$26") (pintype "bidirectional"))
    )
    (net (code "84") (name "/USART2_TX") (class "Default")
      (node (ref "J7") (pin "15") (pinfunction "15_15") (pintype "bidirectional"))
      (node (ref "U4") (pin "P$25") (pinfunction "PA2_P$25") (pintype "bidirectional"))
    )
    (net (code "85") (name "/USART3_CK") (class "Default")
      (node (ref "J5") (pin "1") (pinfunction "1_1") (pintype "bidirectional"))
      (node (ref "U4") (pin "P$57") (pinfunction "PD10_P$57") (pintype "bidirectional"))
    )
    (net (code "86") (name "/USART3_RX") (class "Default")
      (node (ref "J5") (pin "3") (pinfunction "3_3") (pintype "bidirectional"))
      (node (ref "U4") (pin "P$56") (pinfunction "PD9_P$56") (pintype "bidirectional"))
    )
    (net (code "87") (name "/USART3_TX") (class "Default")
      (node (ref "J5") (pin "5") (pinfunction "5_5") (pintype "bidirectional"))
      (node (ref "U4") (pin "P$55") (pinfunction "PD8_P$55") (pintype "bidirectional"))
    )
    (net (code "88") (name "/USB_D+") (class "Default")
      (node (ref "J1") (pin "P$3") (pinfunction "D+_P$3") (pintype "bidirectional"))
      (node (ref "U4") (pin "P$71") (pinfunction "PA12_P$71") (pintype "bidirectional"))
    )
    (net (code "89") (name "/USB_D-") (class "Default")
      (node (ref "J1") (pin "P$2") (pinfunction "D-_P$2") (pintype "bidirectional"))
      (node (ref "U4") (pin "P$70") (pinfunction "PA11_P$70") (pintype "bidirectional"))
    )
    (net (code "90") (name "/USB_ID") (class "Default")
      (node (ref "J1") (pin "P$4") (pinfunction "ID_P$4") (pintype "bidirectional"))
    )
    (net (code "91") (name "/VBAT") (class "Default")
      (node (ref "C8") (pin "2") (pinfunction "2_2") (pintype "passive"))
      (node (ref "J5") (pin "12") (pinfunction "12_12") (pintype "bidirectional"))
      (node (ref "J6") (pin "2") (pinfunction "2_2") (pintype "passive"))
      (node (ref "U1") (pin "P$2") (pinfunction "BAT_P$2") (pintype "bidirectional"))
      (node (ref "U1") (pin "P$3") (pinfunction "MODE_P$3") (pintype "bidirectional"))
      (node (ref "U1") (pin "P$5") (pinfunction "EN1_P$5") (pintype "bidirectional"))
      (node (ref "U1") (pin "P$7") (pinfunction "PVIN_P$7") (pintype "bidirectional"))
    )
    (net (code "92") (name "/VCAP_1") (class "Default")
      (node (ref "C10") (pin "1") (pinfunction "1_1") (pintype "passive"))
      (node (ref "U4") (pin "P$49") (pinfunction "VCAP_1_P$49") (pintype "bidirectional"))
    )
    (net (code "93") (name "/VCAP_2") (class "Default")
      (node (ref "C11") (pin "1") (pinfunction "1_1") (pintype "passive"))
      (node (ref "U4") (pin "P$73") (pinfunction "VCAP_2_P$73") (pintype "bidirectional"))
    )
    (net (code "94") (name "/VUSB") (class "Default")
      (node (ref "C7") (pin "2") (pinfunction "2_2") (pintype "passive"))
      (node (ref "J1") (pin "P$1") (pinfunction "VBUS_P$1") (pintype "bidirectional"))
      (node (ref "J5") (pin "2") (pinfunction "2_2") (pintype "bidirectional"))
      (node (ref "U1") (pin "P$16") (pinfunction "VCC_P$16") (pintype "bidirectional"))
      (node (ref "U4") (pin "P$68") (pinfunction "PA9_P$68") (pintype "bidirectional"))
    )
    (net (code "95") (name "Net-(C1-Pad2)") (class "Default")
      (node (ref "C1") (pin "2") (pinfunction "2_2") (pintype "passive"))
      (node (ref "U2") (pin "P$14") (pinfunction "RES_P$14") (pintype "bidirectional"))
    )
    (net (code "96") (name "Net-(C23-Pad2)") (class "Default")
      (node (ref "C23") (pin "2") (pinfunction "2_2") (pintype "passive"))
      (node (ref "U9") (pin "P$14") (pinfunction "RES_P$14") (pintype "bidirectional"))
    )
    (net (code "97") (name "Net-(L1-1)") (class "Default")
      (node (ref "L1") (pin "P$1") (pinfunction "1_P$1") (pintype "passive"))
      (node (ref "U1") (pin "P$6") (pinfunction "SW1_P$6") (pintype "bidirectional"))
    )
    (net (code "98") (name "Net-(LED1-PadA)") (class "Default")
      (node (ref "LED1") (pin "A") (pinfunction "A_A") (pintype "passive"))
      (node (ref "R11") (pin "1") (pinfunction "1_1") (pintype "passive"))
    )
    (net (code "99") (name "Net-(LED2-PadA)") (class "Default")
      (node (ref "LED2") (pin "A") (pinfunction "A_A") (pintype "passive"))
      (node (ref "R12") (pin "1") (pinfunction "1_1") (pintype "passive"))
    )
    (net (code "100") (name "Net-(LED3-PadA)") (class "Default")
      (node (ref "LED3") (pin "A") (pinfunction "A_A") (pintype "passive"))
      (node (ref "R13") (pin "1") (pinfunction "1_1") (pintype "passive"))
    )
    (net (code "101") (name "Net-(SB2-P$3)") (class "Default")
      (node (ref "SB2") (pin "P$2") (pinfunction "P$3_P$2") (pintype "bidirectional"))
      (node (ref "U4") (pin "P$19") (pinfunction "VDD_P$19") (pintype "bidirectional"))
    )
    (net (code "102") (name "Net-(U1-FB1)") (class "Default")
      (node (ref "C14") (pin "1") (pinfunction "1_1") (pintype "passive"))
      (node (ref "R1") (pin "1") (pinfunction "1_1") (pintype "passive"))
      (node (ref "R2") (pin "2") (pinfunction "2_2") (pintype "passive"))
      (node (ref "U1") (pin "P$4") (pinfunction "FB1_P$4") (pintype "bidirectional"))
    )
    (net (code "103") (name "Net-(U1-PROG)") (class "Default")
      (node (ref "R3") (pin "1") (pinfunction "1_1") (pintype "passive"))
      (node (ref "U1") (pin "P$14") (pinfunction "PROG_P$14") (pintype "bidirectional"))
    )
    (net (code "104") (name "Net-(U7-C1)") (class "Default")
      (node (ref "C19") (pin "2") (pinfunction "2_2") (pintype "passive"))
      (node (ref "U7") (pin "P$6") (pinfunction "C1_P$6") (pintype "bidirectional"))
    )
    (net (code "105") (name "Net-(U7-SETC)") (class "Default")
      (node (ref "C20") (pin "1") (pinfunction "1_1") (pintype "passive"))
      (node (ref "U7") (pin "P$13") (pinfunction "SETC_P$13") (pintype "bidirectional"))
    )
    (net (code "106") (name "Net-(U7-SETP)") (class "Default")
      (node (ref "C20") (pin "2") (pinfunction "2_2") (pintype "passive"))
      (node (ref "U7") (pin "P$12") (pinfunction "SETP_P$12") (pintype "bidirectional"))
    )
    (net (code "107") (name "Net-(U8-C1)") (class "Default")
      (node (ref "C21") (pin "2") (pinfunction "2_2") (pintype "passive"))
      (node (ref "U8") (pin "P$6") (pinfunction "C1_P$6") (pintype "bidirectional"))
    )
    (net (code "108") (name "Net-(U8-SETC)") (class "Default")
      (node (ref "C22") (pin "1") (pinfunction "1_1") (pintype "passive"))
      (node (ref "U8") (pin "P$13") (pinfunction "SETC_P$13") (pintype "bidirectional"))
    )
    (net (code "109") (name "Net-(U8-SETP)") (class "Default")
      (node (ref "C22") (pin "2") (pinfunction "2_2") (pintype "passive"))
      (node (ref "U8") (pin "P$12") (pinfunction "SETP_P$12") (pintype "bidirectional"))
    )
    (net (code "110") (name "unconnected-(U1-FB2-PadP$10)") (class "Default")
      (node (ref "U1") (pin "P$10") (pinfunction "FB2_P$10") (pintype "bidirectional"))
    )
    (net (code "111") (name "unconnected-(U1-SW2-PadP$8)") (class "Default")
      (node (ref "U1") (pin "P$8") (pinfunction "SW2_P$8") (pintype "bidirectional"))
    )
    (net (code "112") (name "unconnected-(U4-PA15-PadP$77)") (class "Default")
      (node (ref "U4") (pin "P$77") (pinfunction "PA15_P$77") (pintype "bidirectional"))
    )
    (net (code "113") (name "unconnected-(U4-PE10-PadP$41)") (class "Default")
      (node (ref "U4") (pin "P$41") (pinfunction "PE10_P$41") (pintype "bidirectional"))
    )
    (net (code "114") (name "unconnected-(U7-RES-PadP$8)") (class "Default")
      (node (ref "U7") (pin "P$8") (pinfunction "RES_P$8") (pintype "bidirectional"))
    )
    (net (code "115") (name "unconnected-(U8-RES-PadP$8)") (class "Default")
      (node (ref "U8") (pin "P$8") (pinfunction "RES_P$8") (pintype "bidirectional"))
    )
  )
)
